# Keyboard.net
KiCad netlist of a schematic drawn in Altium Designer
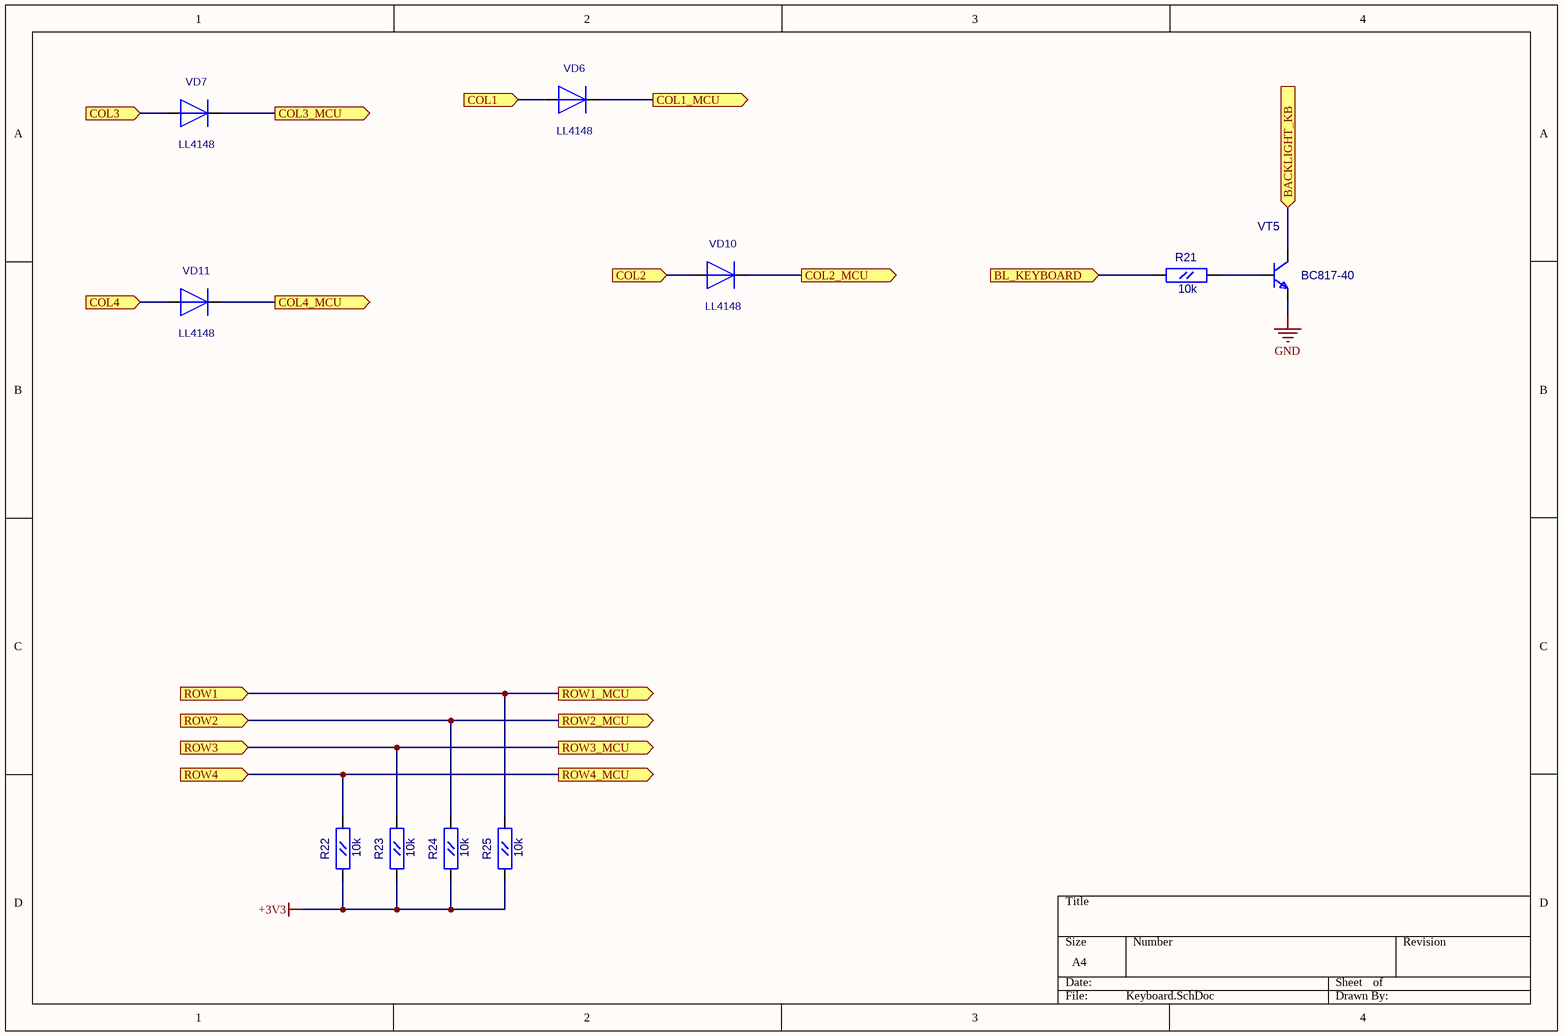
[diagram p0: Keyboard.SchDoc]

(export (version "E")
  (design (tool "Eeschema 10.0.6"))
  (components
    (comp (ref "R21")
      (value "10k")
      (footprint "RC0603")
      (description "RC0603")
      (libsource (lib "gprs_modem_2") (part "RC0603"))
    )
    (comp (ref "R22")
      (value "10k")
      (footprint "RC0603")
      (description "RC0603")
      (libsource (lib "gprs_modem_2") (part "RC0603"))
    )
    (comp (ref "R23")
      (value "10k")
      (footprint "RC0603")
      (description "RC0603")
      (libsource (lib "gprs_modem_2") (part "RC0603"))
    )
    (comp (ref "R24")
      (value "10k")
      (footprint "RC0603")
      (description "RC0603")
      (libsource (lib "gprs_modem_2") (part "RC0603"))
    )
    (comp (ref "R25")
      (value "10k")
      (footprint "RC0603")
      (description "RC0603")
      (libsource (lib "gprs_modem_2") (part "RC0603"))
    )
    (comp (ref "VD6") (value "LL4148") (footprint "SOD-80") (libsource (lib "gprs_modem_2") (part "LL4148")))
    (comp (ref "VD7") (value "LL4148") (footprint "SOD-80") (libsource (lib "gprs_modem_2") (part "LL4148")))
    (comp (ref "VD10") (value "LL4148") (footprint "SOD-80") (libsource (lib "gprs_modem_2") (part "LL4148")))
    (comp (ref "VD11") (value "LL4148") (footprint "SOD-80") (libsource (lib "gprs_modem_2") (part "LL4148")))
    (comp (ref "VT5")
      (value "BC817-40")
      (footprint "SOT-23(123)")
      (description "NPN 500ma transistor")
      (libsource (lib "gprs_modem_2") (part "BC846BLT1"))
    )
  )
  (nets
    (net (code "1") (name "+3V3") (class "Default")
      (node (ref "R22") (pin "1") (pinfunction "A_1") (pintype "passive"))
      (node (ref "R23") (pin "1") (pinfunction "A_1") (pintype "passive"))
      (node (ref "R24") (pin "1") (pinfunction "A_1") (pintype "passive"))
      (node (ref "R25") (pin "1") (pinfunction "A_1") (pintype "passive"))
    )
    (net (code "2") (name "/BACKLIGHT_KB") (class "Default")
      (node (ref "VT5") (pin "3") (pinfunction "C_3") (pintype "passive"))
    )
    (net (code "3") (name "/BL_KEYBOARD") (class "Default")
      (node (ref "R21") (pin "1") (pinfunction "A_1") (pintype "passive"))
    )
    (net (code "4") (name "/COL1") (class "Default")
      (node (ref "VD6") (pin "1") (pinfunction "-_1") (pintype "passive"))
    )
    (net (code "5") (name "/COL1_MCU") (class "Default")
      (node (ref "VD6") (pin "2") (pinfunction "+_2") (pintype "passive"))
    )
    (net (code "6") (name "/COL2") (class "Default")
      (node (ref "VD10") (pin "1") (pinfunction "-_1") (pintype "passive"))
    )
    (net (code "7") (name "/COL2_MCU") (class "Default")
      (node (ref "VD10") (pin "2") (pinfunction "+_2") (pintype "passive"))
    )
    (net (code "8") (name "/COL3") (class "Default")
      (node (ref "VD7") (pin "1") (pinfunction "-_1") (pintype "passive"))
    )
    (net (code "9") (name "/COL3_MCU") (class "Default")
      (node (ref "VD7") (pin "2") (pinfunction "+_2") (pintype "passive"))
    )
    (net (code "10") (name "/COL4") (class "Default")
      (node (ref "VD11") (pin "1") (pinfunction "-_1") (pintype "passive"))
    )
    (net (code "11") (name "/COL4_MCU") (class "Default")
      (node (ref "VD11") (pin "2") (pinfunction "+_2") (pintype "passive"))
    )
    (net (code "12") (name "/ROW1") (class "Default")
      (node (ref "R25") (pin "2") (pinfunction "B_2") (pintype "passive"))
    )
    (net (code "13") (name "/ROW2") (class "Default")
      (node (ref "R24") (pin "2") (pinfunction "B_2") (pintype "passive"))
    )
    (net (code "14") (name "/ROW3") (class "Default")
      (node (ref "R23") (pin "2") (pinfunction "B_2") (pintype "passive"))
    )
    (net (code "15") (name "/ROW4") (class "Default")
      (node (ref "R22") (pin "2") (pinfunction "B_2") (pintype "passive"))
    )
    (net (code "16") (name "GND") (class "Default")
      (node (ref "VT5") (pin "2") (pinfunction "E_2") (pintype "passive"))
    )
    (net (code "17") (name "Net-(R21-B)") (class "Default")
      (node (ref "R21") (pin "2") (pinfunction "B_2") (pintype "passive"))
      (node (ref "VT5") (pin "1") (pinfunction "B_1") (pintype "passive"))
    )
  )
)
